# Dual_Motor_Module.net
KiCad netlist of a schematic drawn in EAGLE
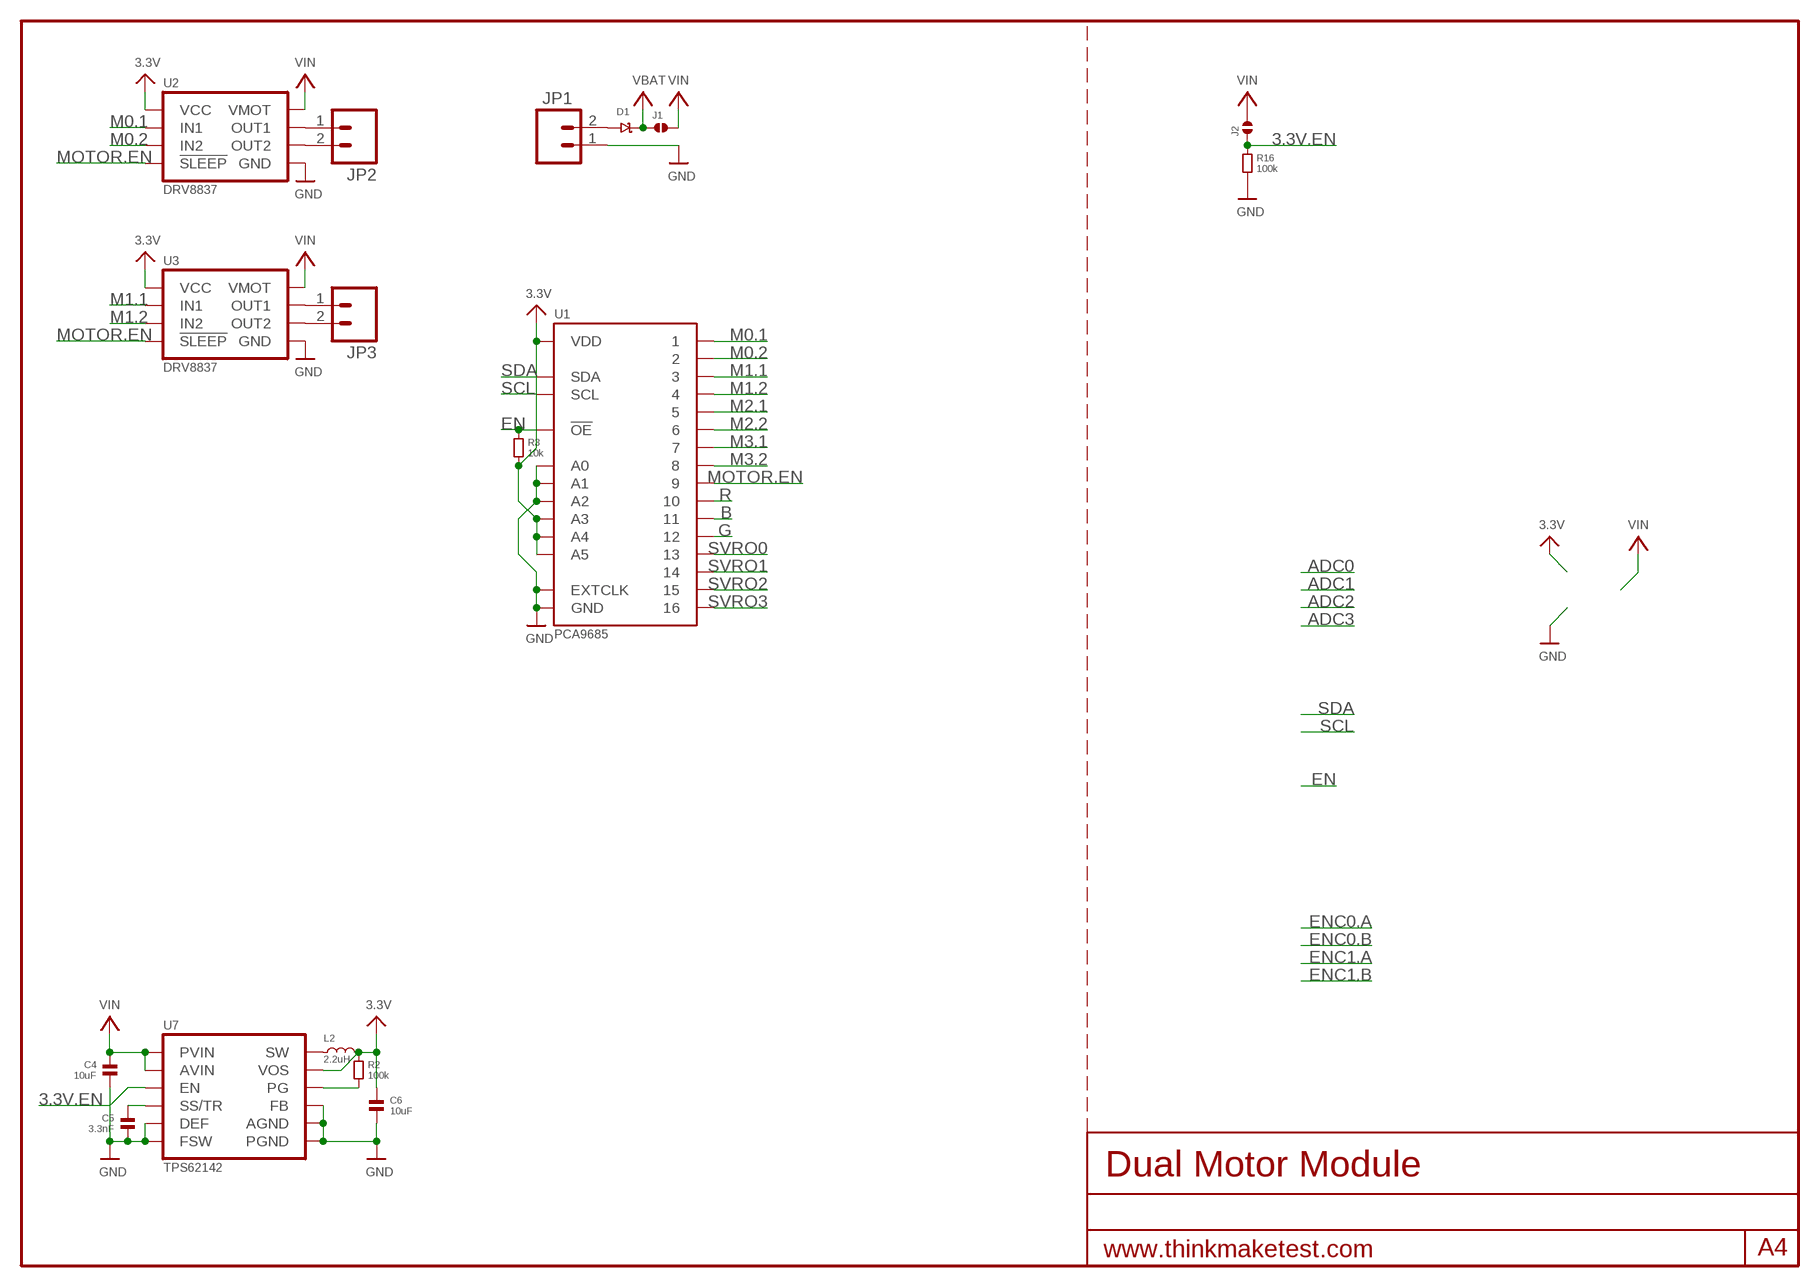
[diagram p0: schematic, sheet 1]

(export (version "E")
  (design (tool "Eeschema 10.0.6"))
  (components
    (comp (ref "C4")
      (value "10uF")
      (footprint "eagle-import:0805")
      (libsource (lib "eagle-import") (part "CAPACITOR.0805"))
    )
    (comp (ref "C5")
      (value "3.3nF")
      (footprint "eagle-import:0603")
      (libsource (lib "eagle-import") (part "CAPACITOR.0603"))
    )
    (comp (ref "C6")
      (value "10uF")
      (footprint "eagle-import:0805")
      (libsource (lib "eagle-import") (part "CAPACITOR.0805"))
    )
    (comp (ref "D1")
      (value "DIODE[SCHOTKY]-SOD123W")
      (footprint "eagle-import:SOD123W")
      (libsource (lib "eagle-import") (part "DIODE[SCHOTKY]-SOD123W"))
    )
    (comp (ref "J1")
      (value "SOLDERJUMPER.2.XL")
      (footprint "eagle-import:2.XL")
      (libsource (lib "eagle-import") (part "SOLDERJUMPER.2.XL"))
    )
    (comp (ref "J2")
      (value "SOLDERJUMPER.2.LRG.PASTE")
      (footprint "eagle-import:2.LRG.PASTE")
      (libsource (lib "eagle-import") (part "SOLDERJUMPER.2.LRG.PASTE"))
    )
    (comp (ref "JP1")
      (value "M023.5MM")
      (footprint "eagle-import:SCREWTERMINAL-3.5MM-2")
      (libsource (lib "eagle-import") (part "M023.5MM"))
    )
    (comp (ref "JP2")
      (value "M023.5MM")
      (footprint "eagle-import:SCREWTERMINAL-3.5MM-2")
      (libsource (lib "eagle-import") (part "M023.5MM"))
    )
    (comp (ref "JP3")
      (value "M023.5MM")
      (footprint "eagle-import:SCREWTERMINAL-3.5MM-2")
      (libsource (lib "eagle-import") (part "M023.5MM"))
    )
    (comp (ref "L2")
      (value "2.2uH")
      (footprint "eagle-import:SRP4020")
      (libsource (lib "eagle-import") (part "INDUCTOR-SRP4020"))
    )
    (comp (ref "R2")
      (value "100k")
      (footprint "eagle-import:0603")
      (libsource (lib "eagle-import") (part "RESISTOR.0603"))
    )
    (comp (ref "R3")
      (value "10k")
      (footprint "eagle-import:0603")
      (libsource (lib "eagle-import") (part "RESISTOR.0603"))
    )
    (comp (ref "R16")
      (value "100k")
      (footprint "eagle-import:0603")
      (libsource (lib "eagle-import") (part "RESISTOR.0603"))
    )
    (comp (ref "U1")
      (value "PCA9685")
      (footprint "eagle-import:HVQFN28")
      (libsource (lib "eagle-import") (part "PCA9685"))
    )
    (comp (ref "U2")
      (value "DRV8837")
      (footprint "eagle-import:DSG")
      (libsource (lib "eagle-import") (part "DRV8837"))
    )
    (comp (ref "U3")
      (value "DRV8837")
      (footprint "eagle-import:DSG")
      (libsource (lib "eagle-import") (part "DRV8837"))
    )
    (comp (ref "U7")
      (value "TPS62142")
      (footprint "eagle-import:RGT")
      (libsource (lib "eagle-import") (part "TPS6214X"))
    )
  )
  (nets
    (net (code "1") (name "/3.3V.EN") (class "Default")
      (node (ref "J2") (pin "1") (pinfunction "1_1") (pintype "bidirectional"))
      (node (ref "R16") (pin "1") (pinfunction "1_1") (pintype "bidirectional"))
      (node (ref "U7") (pin "13") (pinfunction "EN_13") (pintype "bidirectional"))
    )
    (net (code "6") (name "/B") (class "Default")
      (node (ref "U1") (pin "17") (pinfunction "11_17") (pintype "bidirectional"))
    )
    (net (code "7") (name "/EN") (class "Default")
      (node (ref "R3") (pin "1") (pinfunction "1_1") (pintype "bidirectional"))
      (node (ref "U1") (pin "23") (pinfunction "~{OE}_23") (pintype "bidirectional"))
    )
    (net (code "12") (name "/G") (class "Default")
      (node (ref "U1") (pin "18") (pinfunction "12_18") (pintype "bidirectional"))
    )
    (net (code "13") (name "/M0.1") (class "Default")
      (node (ref "U1") (pin "6") (pinfunction "1_6") (pintype "bidirectional"))
      (node (ref "U2") (pin "6") (pinfunction "IN1_6") (pintype "bidirectional"))
    )
    (net (code "14") (name "/M0.2") (class "Default")
      (node (ref "U1") (pin "7") (pinfunction "2_7") (pintype "bidirectional"))
      (node (ref "U2") (pin "5") (pinfunction "IN2_5") (pintype "bidirectional"))
    )
    (net (code "15") (name "/M1.1") (class "Default")
      (node (ref "U1") (pin "8") (pinfunction "3_8") (pintype "bidirectional"))
      (node (ref "U3") (pin "6") (pinfunction "IN1_6") (pintype "bidirectional"))
    )
    (net (code "16") (name "/M1.2") (class "Default")
      (node (ref "U1") (pin "9") (pinfunction "4_9") (pintype "bidirectional"))
      (node (ref "U3") (pin "5") (pinfunction "IN2_5") (pintype "bidirectional"))
    )
    (net (code "17") (name "/M2.1") (class "Default")
      (node (ref "U1") (pin "10") (pinfunction "5_10") (pintype "bidirectional"))
    )
    (net (code "18") (name "/M2.2") (class "Default")
      (node (ref "U1") (pin "11") (pinfunction "6_11") (pintype "bidirectional"))
    )
    (net (code "19") (name "/M3.1") (class "Default")
      (node (ref "U1") (pin "12") (pinfunction "7_12") (pintype "bidirectional"))
    )
    (net (code "20") (name "/M3.2") (class "Default")
      (node (ref "U1") (pin "13") (pinfunction "8_13") (pintype "bidirectional"))
    )
    (net (code "21") (name "/MOTOR.EN") (class "Default")
      (node (ref "U1") (pin "15") (pinfunction "9_15") (pintype "bidirectional"))
      (node (ref "U2") (pin "7") (pinfunction "~{SLEEP}_7") (pintype "bidirectional"))
      (node (ref "U3") (pin "7") (pinfunction "~{SLEEP}_7") (pintype "bidirectional"))
    )
    (net (code "22") (name "/R") (class "Default")
      (node (ref "U1") (pin "16") (pinfunction "10_16") (pintype "bidirectional"))
    )
    (net (code "23") (name "/SCL") (class "Default")
      (node (ref "U1") (pin "26") (pinfunction "SCL_26") (pintype "bidirectional"))
    )
    (net (code "24") (name "/SDA") (class "Default")
      (node (ref "U1") (pin "27") (pinfunction "SDA_27") (pintype "bidirectional"))
    )
    (net (code "25") (name "/SVRO0") (class "Default")
      (node (ref "U1") (pin "19") (pinfunction "13_19") (pintype "bidirectional"))
    )
    (net (code "26") (name "/SVRO1") (class "Default")
      (node (ref "U1") (pin "20") (pinfunction "14_20") (pintype "bidirectional"))
    )
    (net (code "27") (name "/SVRO2") (class "Default")
      (node (ref "U1") (pin "21") (pinfunction "15_21") (pintype "bidirectional"))
    )
    (net (code "28") (name "/SVRO3") (class "Default")
      (node (ref "U1") (pin "22") (pinfunction "16_22") (pintype "bidirectional"))
    )
    (net (code "29") (name "3.3V") (class "Default")
      (node (ref "C6") (pin "1") (pinfunction "1_1") (pintype "bidirectional"))
      (node (ref "L2") (pin "2") (pinfunction "2_2") (pintype "passive"))
      (node (ref "R2") (pin "1") (pinfunction "1_1") (pintype "bidirectional"))
      (node (ref "R3") (pin "2") (pinfunction "2_2") (pintype "bidirectional"))
      (node (ref "U1") (pin "24") (pinfunction "A5_24") (pintype "bidirectional"))
      (node (ref "U1") (pin "28") (pinfunction "VDD_28") (pintype "bidirectional"))
      (node (ref "U1") (pin "4") (pinfunction "A3_4") (pintype "bidirectional"))
      (node (ref "U1") (pin "5") (pinfunction "A4_5") (pintype "bidirectional"))
      (node (ref "U2") (pin "8") (pinfunction "VCC_8") (pintype "bidirectional"))
      (node (ref "U3") (pin "8") (pinfunction "VCC_8") (pintype "bidirectional"))
      (node (ref "U7") (pin "14") (pinfunction "VOS_14") (pintype "bidirectional"))
    )
    (net (code "30") (name "GND") (class "Default")
      (node (ref "C4") (pin "2") (pinfunction "2_2") (pintype "bidirectional"))
      (node (ref "C5") (pin "2") (pinfunction "2_2") (pintype "bidirectional"))
      (node (ref "C6") (pin "2") (pinfunction "2_2") (pintype "bidirectional"))
      (node (ref "JP1") (pin "1") (pinfunction "1_1") (pintype "passive"))
      (node (ref "R16") (pin "2") (pinfunction "2_2") (pintype "bidirectional"))
      (node (ref "U1") (pin "1") (pinfunction "A0_1") (pintype "bidirectional"))
      (node (ref "U1") (pin "14") (pinfunction "GND_14") (pintype "bidirectional"))
      (node (ref "U1") (pin "2") (pinfunction "A1_2") (pintype "bidirectional"))
      (node (ref "U1") (pin "25") (pinfunction "EXTCLK_25") (pintype "bidirectional"))
      (node (ref "U1") (pin "3") (pinfunction "A2_3") (pintype "bidirectional"))
      (node (ref "U1") (pin "PAD") (pinfunction "GND_PAD") (pintype "bidirectional"))
      (node (ref "U2") (pin "4") (pinfunction "GND_4") (pintype "bidirectional"))
      (node (ref "U2") (pin "PAD") (pinfunction "GND_PAD") (pintype "bidirectional"))
      (node (ref "U3") (pin "4") (pinfunction "GND_4") (pintype "bidirectional"))
      (node (ref "U3") (pin "PAD") (pinfunction "GND_PAD") (pintype "bidirectional"))
      (node (ref "U7") (pin "15") (pinfunction "PGND_15") (pintype "bidirectional"))
      (node (ref "U7") (pin "16") (pinfunction "PGND_16") (pintype "bidirectional"))
      (node (ref "U7") (pin "5") (pinfunction "FB_5") (pintype "bidirectional"))
      (node (ref "U7") (pin "6") (pinfunction "AGND_6") (pintype "bidirectional"))
      (node (ref "U7") (pin "7") (pinfunction "FSW_7") (pintype "bidirectional"))
      (node (ref "U7") (pin "8") (pinfunction "DEF_8") (pintype "bidirectional"))
      (node (ref "U7") (pin "PAD") (pinfunction "AGND_PAD") (pintype "bidirectional"))
    )
    (net (code "31") (name "Net-(D1-1)") (class "Default")
      (node (ref "D1") (pin "P$1") (pinfunction "1_P$1") (pintype "bidirectional"))
      (node (ref "JP1") (pin "2") (pinfunction "2_2") (pintype "passive"))
    )
    (net (code "32") (name "Net-(L2-Pad1)") (class "Default")
      (node (ref "L2") (pin "1") (pinfunction "1_1") (pintype "passive"))
      (node (ref "U7") (pin "1") (pinfunction "SW_1") (pintype "bidirectional"))
      (node (ref "U7") (pin "2") (pinfunction "SW_2") (pintype "bidirectional"))
      (node (ref "U7") (pin "3") (pinfunction "SW_3") (pintype "bidirectional"))
    )
    (net (code "33") (name "Net-(U2-OUT1)") (class "Default")
      (node (ref "JP2") (pin "1") (pinfunction "1_1") (pintype "passive"))
      (node (ref "U2") (pin "2") (pinfunction "OUT1_2") (pintype "bidirectional"))
    )
    (net (code "34") (name "Net-(U2-OUT2)") (class "Default")
      (node (ref "JP2") (pin "2") (pinfunction "2_2") (pintype "passive"))
      (node (ref "U2") (pin "3") (pinfunction "OUT2_3") (pintype "bidirectional"))
    )
    (net (code "35") (name "Net-(U3-OUT1)") (class "Default")
      (node (ref "JP3") (pin "1") (pinfunction "1_1") (pintype "passive"))
      (node (ref "U3") (pin "2") (pinfunction "OUT1_2") (pintype "bidirectional"))
    )
    (net (code "36") (name "Net-(U3-OUT2)") (class "Default")
      (node (ref "JP3") (pin "2") (pinfunction "2_2") (pintype "passive"))
      (node (ref "U3") (pin "3") (pinfunction "OUT2_3") (pintype "bidirectional"))
    )
    (net (code "37") (name "Net-(U7-PG)") (class "Default")
      (node (ref "R2") (pin "2") (pinfunction "2_2") (pintype "bidirectional"))
      (node (ref "U7") (pin "4") (pinfunction "PG_4") (pintype "bidirectional"))
    )
    (net (code "38") (name "Net-(U7-SS{slash}TR)") (class "Default")
      (node (ref "C5") (pin "1") (pinfunction "1_1") (pintype "bidirectional"))
      (node (ref "U7") (pin "9") (pinfunction "SS/TR_9") (pintype "bidirectional"))
    )
    (net (code "39") (name "VBAT") (class "Default")
      (node (ref "D1") (pin "P$2") (pinfunction "2_P$2") (pintype "bidirectional"))
      (node (ref "J1") (pin "1") (pinfunction "1_1") (pintype "bidirectional"))
    )
    (net (code "40") (name "VIN") (class "Default")
      (node (ref "C4") (pin "1") (pinfunction "1_1") (pintype "bidirectional"))
      (node (ref "J1") (pin "2") (pinfunction "2_2") (pintype "bidirectional"))
      (node (ref "J2") (pin "2") (pinfunction "2_2") (pintype "bidirectional"))
      (node (ref "U2") (pin "1") (pinfunction "VMOT_1") (pintype "bidirectional"))
      (node (ref "U3") (pin "1") (pinfunction "VMOT_1") (pintype "bidirectional"))
      (node (ref "U7") (pin "10") (pinfunction "AVIN_10") (pintype "bidirectional"))
      (node (ref "U7") (pin "11") (pinfunction "PVIN_11") (pintype "bidirectional"))
      (node (ref "U7") (pin "12") (pinfunction "PVIN_12") (pintype "bidirectional"))
    )
  )
)
